# Sheet2_W5500.net
KiCad netlist of a schematic drawn in Altium Designer
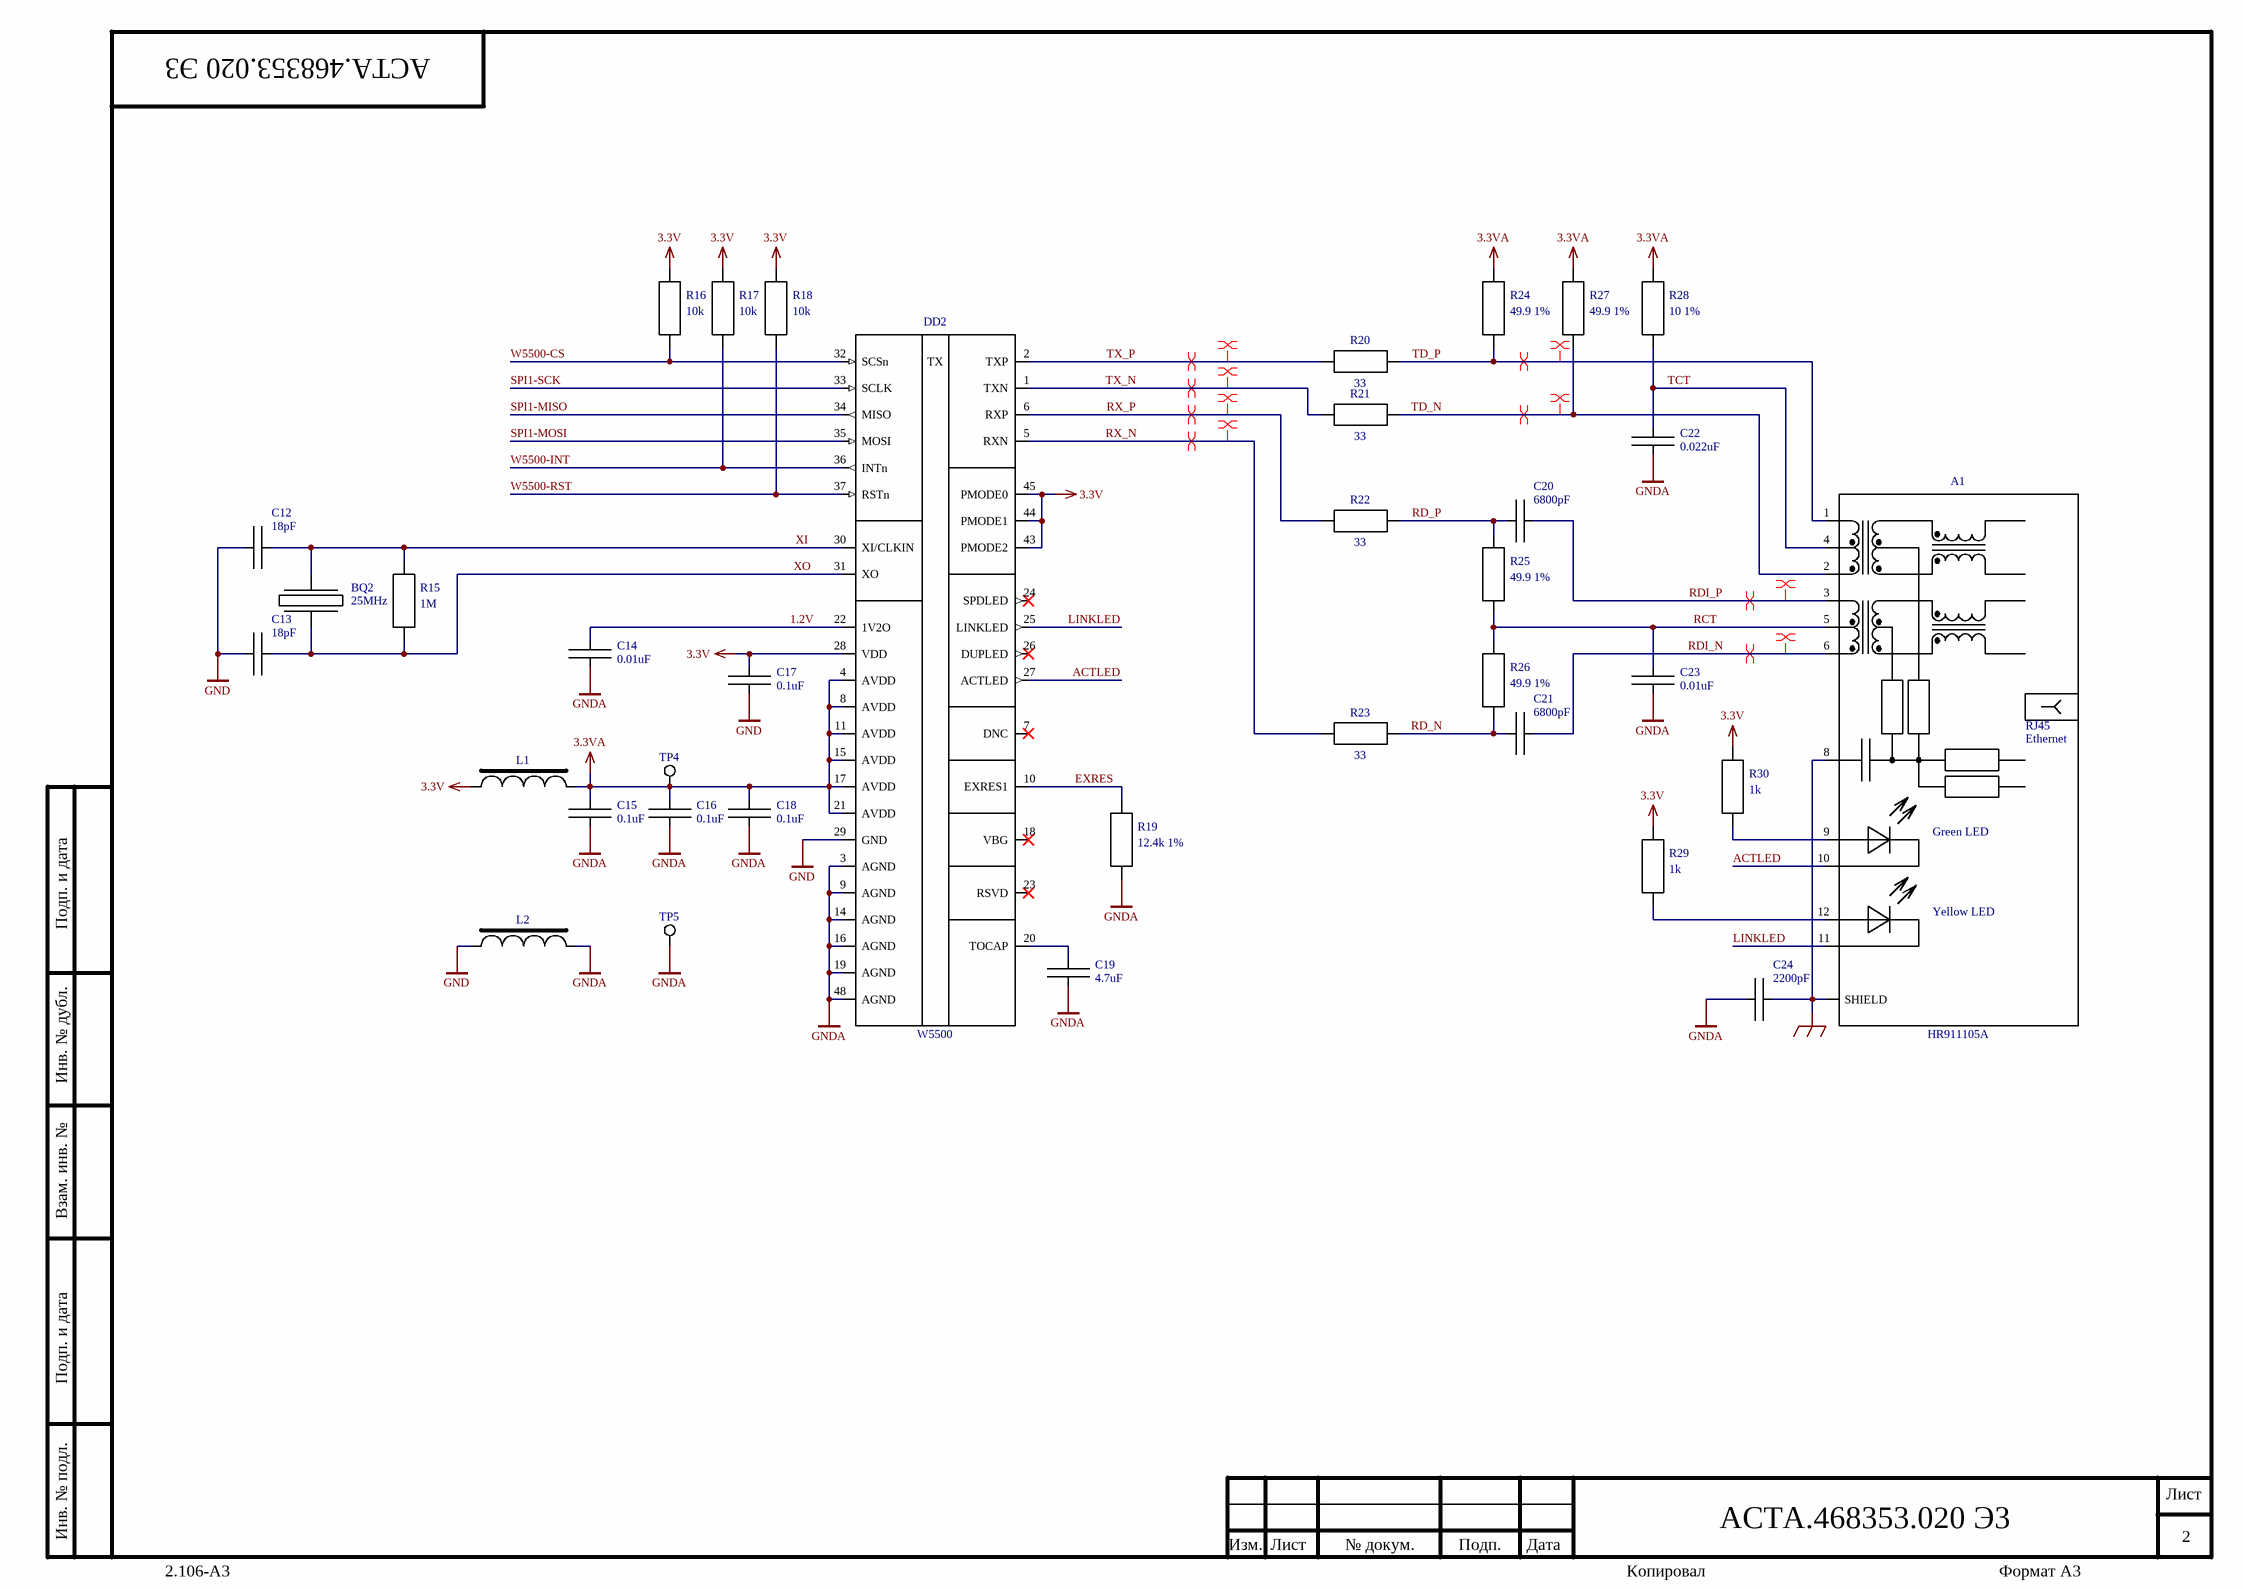
[diagram p0: Sheet2_W5500.SchDoc]

(export (version "E")
  (design (tool "Eeschema 10.0.6"))
  (components
    (comp (ref "A1")
      (value "HR911105A")
      (footprint "HR911105A")
      (description "Ethernet Connector 10/100 1x1 Tab Down RJ45 w/mag G/Y LED")
      (libsource (lib "Devices") (part "HR911105A"))
    )
    (comp (ref "BQ2")
      (value "25MHz")
      (footprint "HT-49S")
      (fields (field (name "Comment") "HT-49S_Rated"))
      (libsource (lib "Resonators") (part "HT-49S_Rated"))
    )
    (comp (ref "C12")
      (value "18pF")
      (footprint "CAP0805")
      (fields (field (name "Comment") "CAP0805_Rated"))
      (libsource (lib "Ceramic_Capacitors") (part "CAP0805_Rated"))
    )
    (comp (ref "C13")
      (value "18pF")
      (footprint "CAP0805")
      (fields (field (name "Comment") "CAP0805_Rated"))
      (libsource (lib "Ceramic_Capacitors") (part "CAP0805_Rated"))
    )
    (comp (ref "C14")
      (value "0.01uF")
      (footprint "CAP0805")
      (fields (field (name "Comment") "CAP0805_Rated"))
      (libsource (lib "Ceramic_Capacitors") (part "CAP0805_Rated"))
    )
    (comp (ref "C15")
      (value "0.1uF")
      (footprint "CAP0805")
      (fields (field (name "Comment") "CAP0805_Rated"))
      (libsource (lib "Ceramic_Capacitors") (part "CAP0805_Rated"))
    )
    (comp (ref "C16")
      (value "0.1uF")
      (footprint "CAP0805")
      (fields (field (name "Comment") "CAP0805_Rated"))
      (libsource (lib "Ceramic_Capacitors") (part "CAP0805_Rated"))
    )
    (comp (ref "C17")
      (value "0.1uF")
      (footprint "CAP0805")
      (fields (field (name "Comment") "CAP0805_Rated"))
      (libsource (lib "Ceramic_Capacitors") (part "CAP0805_Rated"))
    )
    (comp (ref "C18")
      (value "0.1uF")
      (footprint "CAP0805")
      (fields (field (name "Comment") "CAP0805_Rated"))
      (libsource (lib "Ceramic_Capacitors") (part "CAP0805_Rated"))
    )
    (comp (ref "C19")
      (value "4.7uF")
      (footprint "CAP1206")
      (fields (field (name "Comment") "CAP1206_Rated"))
      (libsource (lib "Ceramic_Capacitors") (part "CAP1206_Rated"))
    )
    (comp (ref "C20")
      (value "6800pF")
      (footprint "CAP0805")
      (fields (field (name "Comment") "CAP0805_Rated"))
      (libsource (lib "Ceramic_Capacitors") (part "CAP0805_Rated"))
    )
    (comp (ref "C21")
      (value "6800pF")
      (footprint "CAP0805")
      (fields (field (name "Comment") "CAP0805_Rated"))
      (libsource (lib "Ceramic_Capacitors") (part "CAP0805_Rated"))
    )
    (comp (ref "C22")
      (value "0.022uF")
      (footprint "CAP0805")
      (fields (field (name "Comment") "CAP0805_Rated"))
      (libsource (lib "Ceramic_Capacitors") (part "CAP0805_Rated"))
    )
    (comp (ref "C23")
      (value "0.01uF")
      (footprint "CAP0805")
      (fields (field (name "Comment") "CAP0805_Rated"))
      (libsource (lib "Ceramic_Capacitors") (part "CAP0805_Rated"))
    )
    (comp (ref "C24")
      (value "2200pF")
      (footprint "CAP1812")
      (fields (field (name "Comment") "CAP1812_Rated"))
      (libsource (lib "Ceramic_Capacitors") (part "CAP1812_Rated"))
    )
    (comp (ref "DD2")
      (value "W5500")
      (footprint "LQFP-48")
      (description "Ethernet ICs 3in1 Enet Controller TCP/IP +MAC+PHY")
      (libsource (lib "Interface_ICs") (part "W5500"))
    )
    (comp (ref "L1")
      (value "BLM21BD121SN1D")
      (footprint "IND0805")
      (description "Ferrite Bead 0805 120 Ohm")
      (fields (field (name "MANUFACTURER") "Murata") (field (name "TOLERANCE") "25%"))
      (libsource (lib "Inductors") (part "BLM21BD121SN1D"))
    )
    (comp (ref "L2")
      (value "BLM21BD121SN1D")
      (footprint "IND0805")
      (description "Ferrite Bead 0805 120 Ohm")
      (fields (field (name "MANUFACTURER") "Murata") (field (name "TOLERANCE") "25%"))
      (libsource (lib "Inductors") (part "BLM21BD121SN1D"))
    )
    (comp (ref "R15")
      (value "1M")
      (footprint "RES0805")
      (fields (field (name "TOLERANCE") "5%") (field (name "Comment") "RES0805_Rated"))
      (libsource (lib "Resistors") (part "RES0805_Rated"))
    )
    (comp (ref "R16")
      (value "10k")
      (footprint "RES0805")
      (fields (field (name "TOLERANCE") "5%") (field (name "Comment") "RES0805_Rated"))
      (libsource (lib "Resistors") (part "RES0805_Rated"))
    )
    (comp (ref "R17")
      (value "10k")
      (footprint "RES0805")
      (fields (field (name "TOLERANCE") "5%") (field (name "Comment") "RES0805_Rated"))
      (libsource (lib "Resistors") (part "RES0805_Rated"))
    )
    (comp (ref "R18")
      (value "10k")
      (footprint "RES0805")
      (fields (field (name "TOLERANCE") "5%") (field (name "Comment") "RES0805_Rated"))
      (libsource (lib "Resistors") (part "RES0805_Rated"))
    )
    (comp (ref "R19")
      (value "12.4k 1%")
      (footprint "RES0805")
      (fields (field (name "TOLERANCE") "5%") (field (name "Comment") "RES0805_Rated"))
      (libsource (lib "Resistors") (part "RES0805_Rated"))
    )
    (comp (ref "R20")
      (value "33")
      (footprint "RES0805")
      (fields (field (name "TOLERANCE") "5%") (field (name "Comment") "RES0805_Rated"))
      (libsource (lib "") (part "RES0805_Rated_1"))
    )
    (comp (ref "R21")
      (value "33")
      (footprint "RES0805")
      (fields (field (name "TOLERANCE") "5%") (field (name "Comment") "RES0805_Rated"))
      (libsource (lib "") (part "RES0805_Rated_1"))
    )
    (comp (ref "R22")
      (value "33")
      (footprint "RES0805")
      (fields (field (name "TOLERANCE") "5%") (field (name "Comment") "RES0805_Rated"))
      (libsource (lib "") (part "RES0805_Rated_1"))
    )
    (comp (ref "R23")
      (value "33")
      (footprint "RES0805")
      (fields (field (name "TOLERANCE") "5%") (field (name "Comment") "RES0805_Rated"))
      (libsource (lib "") (part "RES0805_Rated_1"))
    )
    (comp (ref "R24")
      (value "49.9 1%")
      (footprint "RES0805")
      (fields (field (name "TOLERANCE") "5%") (field (name "Comment") "RES0805_Rated"))
      (libsource (lib "Resistors") (part "RES0805_Rated"))
    )
    (comp (ref "R25")
      (value "49.9 1%")
      (footprint "RES0805")
      (fields (field (name "TOLERANCE") "5%") (field (name "Comment") "RES0805_Rated"))
      (libsource (lib "Resistors") (part "RES0805_Rated"))
    )
    (comp (ref "R26")
      (value "49.9 1%")
      (footprint "RES0805")
      (fields (field (name "TOLERANCE") "5%") (field (name "Comment") "RES0805_Rated"))
      (libsource (lib "Resistors") (part "RES0805_Rated"))
    )
    (comp (ref "R27")
      (value "49.9 1%")
      (footprint "RES0805")
      (fields (field (name "TOLERANCE") "5%") (field (name "Comment") "RES0805_Rated"))
      (libsource (lib "Resistors") (part "RES0805_Rated"))
    )
    (comp (ref "R28")
      (value "10 1%")
      (footprint "RES0805")
      (fields (field (name "TOLERANCE") "5%") (field (name "Comment") "RES0805_Rated"))
      (libsource (lib "Resistors") (part "RES0805_Rated"))
    )
    (comp (ref "R29")
      (value "1k")
      (footprint "RES0805")
      (fields (field (name "TOLERANCE") "5%") (field (name "Comment") "RES0805_Rated"))
      (libsource (lib "Resistors") (part "RES0805_Rated"))
    )
    (comp (ref "R30")
      (value "1k")
      (footprint "RES0805")
      (fields (field (name "TOLERANCE") "5%") (field (name "Comment") "RES0805_Rated"))
      (libsource (lib "Resistors") (part "RES0805_Rated"))
    )
    (comp (ref "TP4")
      (value "TestPad")
      (footprint "PAD-TH-OCT1x1-0.5")
      (description "TestPoint on PCB")
      (libsource (lib "Connectors") (part "TestPad"))
    )
    (comp (ref "TP5")
      (value "TestPad")
      (footprint "PAD-TH-OCT1x1-0.5")
      (description "TestPoint on PCB")
      (libsource (lib "Connectors") (part "TestPad"))
    )
  )
  (nets
    (net (code "1") (name "/1.2V") (class "Default")
      (node (ref "C14") (pin "1") (pinfunction "1_1") (pintype "passive"))
      (node (ref "DD2") (pin "22") (pinfunction "1V2O_22") (pintype "power_in"))
    )
    (net (code "2") (name "/ACTLED") (class "Default")
      (node (ref "A1") (pin "10") (pinfunction "LED1-K_10") (pintype "passive"))
      (node (ref "DD2") (pin "27") (pinfunction "ACTLED_27") (pintype "output"))
    )
    (net (code "3") (name "/EXRES") (class "Default")
      (node (ref "DD2") (pin "10") (pinfunction "EXRES1_10") (pintype "passive"))
      (node (ref "R19") (pin "2") (pinfunction "2_2") (pintype "passive"))
    )
    (net (code "4") (name "/LINKLED") (class "Default")
      (node (ref "A1") (pin "11") (pinfunction "LED2-A_11") (pintype "passive"))
      (node (ref "DD2") (pin "25") (pinfunction "LINKLED_25") (pintype "output"))
    )
    (net (code "5") (name "/RCT") (class "Default")
      (node (ref "A1") (pin "5") (pinfunction "CT_5") (pintype "passive"))
      (node (ref "C23") (pin "1") (pinfunction "1_1") (pintype "passive"))
      (node (ref "R25") (pin "1") (pinfunction "1_1") (pintype "passive"))
      (node (ref "R26") (pin "2") (pinfunction "2_2") (pintype "passive"))
    )
    (net (code "6") (name "/RDI_N") (class "Default")
      (node (ref "A1") (pin "6") (pinfunction "RD-_6") (pintype "passive"))
      (node (ref "C21") (pin "2") (pinfunction "2_2") (pintype "passive"))
    )
    (net (code "7") (name "/RDI_P") (class "Default")
      (node (ref "A1") (pin "3") (pinfunction "RD+_3") (pintype "passive"))
      (node (ref "C20") (pin "2") (pinfunction "2_2") (pintype "passive"))
    )
    (net (code "8") (name "/RD_N") (class "Default")
      (node (ref "C21") (pin "1") (pinfunction "1_1") (pintype "passive"))
      (node (ref "R23") (pin "2") (pinfunction "2_2") (pintype "passive"))
      (node (ref "R26") (pin "1") (pinfunction "1_1") (pintype "passive"))
    )
    (net (code "9") (name "/RD_P") (class "Default")
      (node (ref "C20") (pin "1") (pinfunction "1_1") (pintype "passive"))
      (node (ref "R22") (pin "2") (pinfunction "2_2") (pintype "passive"))
      (node (ref "R25") (pin "2") (pinfunction "2_2") (pintype "passive"))
    )
    (net (code "10") (name "/RX_N") (class "Default")
      (node (ref "DD2") (pin "5") (pinfunction "RXN_5") (pintype "passive"))
      (node (ref "R23") (pin "1") (pinfunction "1_1") (pintype "passive"))
    )
    (net (code "11") (name "/RX_P") (class "Default")
      (node (ref "DD2") (pin "6") (pinfunction "RXP_6") (pintype "passive"))
      (node (ref "R22") (pin "1") (pinfunction "1_1") (pintype "passive"))
    )
    (net (code "12") (name "/SPI1-MISO") (class "Default")
      (node (ref "DD2") (pin "34") (pinfunction "MISO_34") (pintype "output"))
    )
    (net (code "13") (name "/SPI1-MOSI") (class "Default")
      (node (ref "DD2") (pin "35") (pinfunction "MOSI_35") (pintype "input"))
    )
    (net (code "14") (name "/SPI1-SCK") (class "Default")
      (node (ref "DD2") (pin "33") (pinfunction "SCLK_33") (pintype "input"))
    )
    (net (code "15") (name "/TCT") (class "Default")
      (node (ref "A1") (pin "4") (pinfunction "CT_4") (pintype "passive"))
      (node (ref "C22") (pin "1") (pinfunction "1_1") (pintype "passive"))
      (node (ref "R28") (pin "1") (pinfunction "1_1") (pintype "passive"))
    )
    (net (code "16") (name "/TD_N") (class "Default")
      (node (ref "A1") (pin "2") (pinfunction "TD-_2") (pintype "passive"))
      (node (ref "R21") (pin "2") (pinfunction "2_2") (pintype "passive"))
      (node (ref "R27") (pin "1") (pinfunction "1_1") (pintype "passive"))
    )
    (net (code "17") (name "/TD_P") (class "Default")
      (node (ref "A1") (pin "1") (pinfunction "TD+_1") (pintype "passive"))
      (node (ref "R20") (pin "2") (pinfunction "2_2") (pintype "passive"))
      (node (ref "R24") (pin "1") (pinfunction "1_1") (pintype "passive"))
    )
    (net (code "18") (name "/TX_N") (class "Default")
      (node (ref "DD2") (pin "1") (pinfunction "TXN_1") (pintype "passive"))
      (node (ref "R21") (pin "1") (pinfunction "1_1") (pintype "passive"))
    )
    (net (code "19") (name "/TX_P") (class "Default")
      (node (ref "DD2") (pin "2") (pinfunction "TXP_2") (pintype "passive"))
      (node (ref "R20") (pin "1") (pinfunction "1_1") (pintype "passive"))
    )
    (net (code "20") (name "/W5500-CS") (class "Default")
      (node (ref "DD2") (pin "32") (pinfunction "SCSn_32") (pintype "input"))
      (node (ref "R16") (pin "1") (pinfunction "1_1") (pintype "passive"))
    )
    (net (code "21") (name "/W5500-INT") (class "Default")
      (node (ref "DD2") (pin "36") (pinfunction "INTn_36") (pintype "output"))
      (node (ref "R17") (pin "1") (pinfunction "1_1") (pintype "passive"))
    )
    (net (code "22") (name "/W5500-RST") (class "Default")
      (node (ref "DD2") (pin "37") (pinfunction "RSTn_37") (pintype "input"))
      (node (ref "R18") (pin "1") (pinfunction "1_1") (pintype "passive"))
    )
    (net (code "23") (name "/XI") (class "Default")
      (node (ref "BQ2") (pin "1") (pinfunction "1_1") (pintype "passive"))
      (node (ref "C12") (pin "2") (pinfunction "2_2") (pintype "passive"))
      (node (ref "DD2") (pin "30") (pinfunction "XI/CLKIN_30") (pintype "passive"))
      (node (ref "R15") (pin "2") (pinfunction "2_2") (pintype "passive"))
    )
    (net (code "24") (name "/XO") (class "Default")
      (node (ref "BQ2") (pin "2") (pinfunction "2_2") (pintype "passive"))
      (node (ref "C13") (pin "2") (pinfunction "2_2") (pintype "passive"))
      (node (ref "DD2") (pin "31") (pinfunction "XO_31") (pintype "passive"))
      (node (ref "R15") (pin "1") (pinfunction "1_1") (pintype "passive"))
    )
    (net (code "25") (name "3.3V") (class "Default")
      (node (ref "C17") (pin "1") (pinfunction "1_1") (pintype "passive"))
      (node (ref "DD2") (pin "28") (pinfunction "VDD_28") (pintype "power_in"))
      (node (ref "DD2") (pin "43") (pinfunction "PMODE2_43") (pintype "passive"))
      (node (ref "DD2") (pin "44") (pinfunction "PMODE1_44") (pintype "passive"))
      (node (ref "DD2") (pin "45") (pinfunction "PMODE0_45") (pintype "passive"))
      (node (ref "L1") (pin "1") (pinfunction "1_1") (pintype "passive"))
      (node (ref "R16") (pin "2") (pinfunction "2_2") (pintype "passive"))
      (node (ref "R17") (pin "2") (pinfunction "2_2") (pintype "passive"))
      (node (ref "R18") (pin "2") (pinfunction "2_2") (pintype "passive"))
      (node (ref "R29") (pin "2") (pinfunction "2_2") (pintype "passive"))
      (node (ref "R30") (pin "2") (pinfunction "2_2") (pintype "passive"))
    )
    (net (code "26") (name "3.3VA") (class "Default")
      (node (ref "C15") (pin "1") (pinfunction "1_1") (pintype "passive"))
      (node (ref "C16") (pin "1") (pinfunction "1_1") (pintype "passive"))
      (node (ref "C18") (pin "1") (pinfunction "1_1") (pintype "passive"))
      (node (ref "DD2") (pin "11") (pinfunction "AVDD_11") (pintype "power_in"))
      (node (ref "DD2") (pin "15") (pinfunction "AVDD_15") (pintype "power_in"))
      (node (ref "DD2") (pin "17") (pinfunction "AVDD_17") (pintype "power_in"))
      (node (ref "DD2") (pin "21") (pinfunction "AVDD_21") (pintype "power_in"))
      (node (ref "DD2") (pin "4") (pinfunction "AVDD_4") (pintype "power_in"))
      (node (ref "DD2") (pin "8") (pinfunction "AVDD_8") (pintype "power_in"))
      (node (ref "L1") (pin "2") (pinfunction "2_2") (pintype "passive"))
      (node (ref "R24") (pin "2") (pinfunction "2_2") (pintype "passive"))
      (node (ref "R27") (pin "2") (pinfunction "2_2") (pintype "passive"))
      (node (ref "R28") (pin "2") (pinfunction "2_2") (pintype "passive"))
      (node (ref "TP4") (pin "1") (pinfunction "1_1") (pintype "passive"))
    )
    (net (code "27") (name "EARTH") (class "Default")
      (node (ref "A1") (pin "8") (pinfunction "GND_8") (pintype "power_in"))
      (node (ref "A1") (pin "SHIELD") (pinfunction "SHIELD_SHIELD") (pintype "passive"))
      (node (ref "C24") (pin "2") (pinfunction "2_2") (pintype "passive"))
    )
    (net (code "28") (name "GND") (class "Default")
      (node (ref "C12") (pin "1") (pinfunction "1_1") (pintype "passive"))
      (node (ref "C13") (pin "1") (pinfunction "1_1") (pintype "passive"))
      (node (ref "C17") (pin "2") (pinfunction "2_2") (pintype "passive"))
      (node (ref "DD2") (pin "29") (pinfunction "GND_29") (pintype "power_in"))
      (node (ref "L2") (pin "1") (pinfunction "1_1") (pintype "passive"))
    )
    (net (code "29") (name "GNDA") (class "Default")
      (node (ref "C14") (pin "2") (pinfunction "2_2") (pintype "passive"))
      (node (ref "C15") (pin "2") (pinfunction "2_2") (pintype "passive"))
      (node (ref "C16") (pin "2") (pinfunction "2_2") (pintype "passive"))
      (node (ref "C18") (pin "2") (pinfunction "2_2") (pintype "passive"))
      (node (ref "C19") (pin "2") (pinfunction "2_2") (pintype "passive"))
      (node (ref "C22") (pin "2") (pinfunction "2_2") (pintype "passive"))
      (node (ref "C23") (pin "2") (pinfunction "2_2") (pintype "passive"))
      (node (ref "C24") (pin "1") (pinfunction "1_1") (pintype "passive"))
      (node (ref "DD2") (pin "14") (pinfunction "AGND_14") (pintype "power_in"))
      (node (ref "DD2") (pin "16") (pinfunction "AGND_16") (pintype "power_in"))
      (node (ref "DD2") (pin "19") (pinfunction "AGND_19") (pintype "power_in"))
      (node (ref "DD2") (pin "3") (pinfunction "AGND_3") (pintype "power_in"))
      (node (ref "DD2") (pin "48") (pinfunction "AGND_48") (pintype "power_in"))
      (node (ref "DD2") (pin "9") (pinfunction "AGND_9") (pintype "power_in"))
      (node (ref "L2") (pin "2") (pinfunction "2_2") (pintype "passive"))
      (node (ref "R19") (pin "1") (pinfunction "1_1") (pintype "passive"))
      (node (ref "TP5") (pin "1") (pinfunction "1_1") (pintype "passive"))
    )
    (net (code "30") (name "Net-(A1-LED1-A)") (class "Default")
      (node (ref "A1") (pin "9") (pinfunction "LED1-A_9") (pintype "passive"))
      (node (ref "R30") (pin "1") (pinfunction "1_1") (pintype "passive"))
    )
    (net (code "31") (name "Net-(A1-LED2-K)") (class "Default")
      (node (ref "A1") (pin "12") (pinfunction "LED2-K_12") (pintype "passive"))
      (node (ref "R29") (pin "1") (pinfunction "1_1") (pintype "passive"))
    )
    (net (code "32") (name "Net-(DD2-TOCAP)") (class "Default")
      (node (ref "C19") (pin "1") (pinfunction "1_1") (pintype "passive"))
      (node (ref "DD2") (pin "20") (pinfunction "TOCAP_20") (pintype "passive"))
    )
    (net (code "33") (name "unconnected-(DD2-DNC-Pad7)") (class "Default")
      (node (ref "DD2") (pin "7") (pinfunction "DNC_7") (pintype "passive+no_connect"))
    )
    (net (code "34") (name "unconnected-(DD2-DUPLED-Pad26)") (class "Default")
      (node (ref "DD2") (pin "26") (pinfunction "DUPLED_26") (pintype "output+no_connect"))
    )
    (net (code "35") (name "unconnected-(DD2-RSVD-Pad23)") (class "Default")
      (node (ref "DD2") (pin "23") (pinfunction "RSVD_23") (pintype "passive+no_connect"))
    )
    (net (code "36") (name "unconnected-(DD2-SPDLED-Pad24)") (class "Default")
      (node (ref "DD2") (pin "24") (pinfunction "SPDLED_24") (pintype "output+no_connect"))
    )
    (net (code "37") (name "unconnected-(DD2-VBG-Pad18)") (class "Default")
      (node (ref "DD2") (pin "18") (pinfunction "VBG_18") (pintype "passive+no_connect"))
    )
  )
)
